# Power.net
KiCad netlist of a schematic drawn in Altium Designer
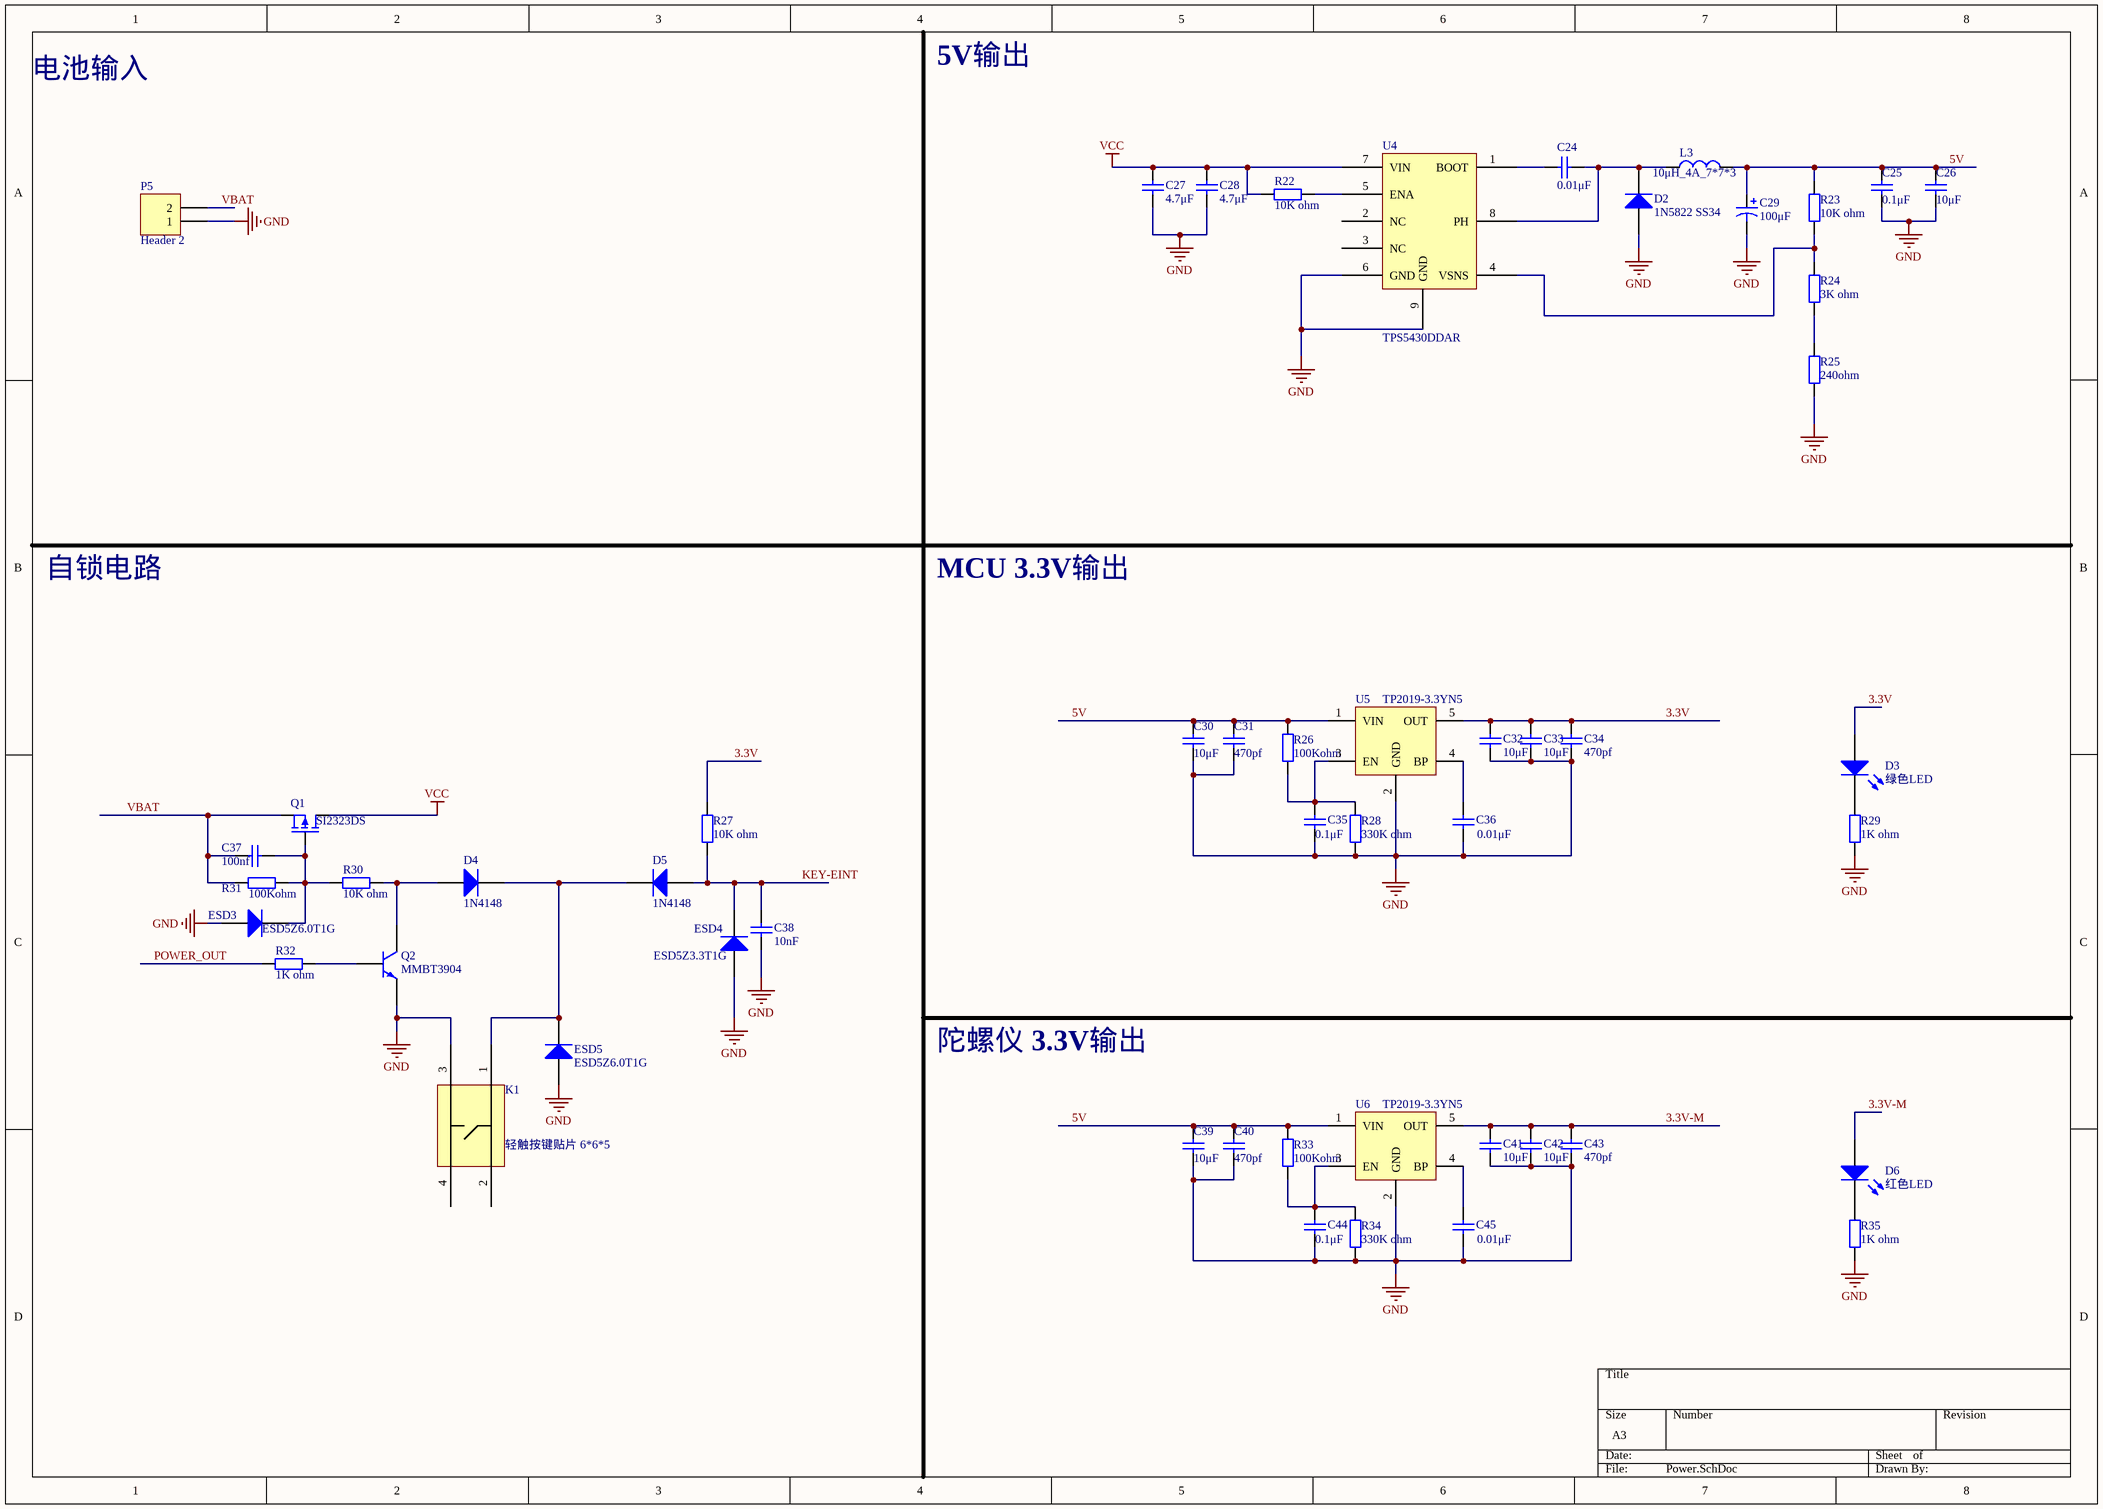
[diagram p0: Power.SchDoc]

(export (version "E")
  (design (tool "Eeschema 10.0.6"))
  (components
    (comp (ref "C24")
      (value "0.01μF")
      (footprint "0603C")
      (description "0.01μF_50V,C0G,5%")
      (libsource (lib "Yang_Lib") (part "Cap_0.01μF_50V_0603"))
    )
    (comp (ref "C25")
      (value "0.1μF")
      (footprint "0603C")
      (description "0.1μF_50V,X7R,±5%")
      (libsource (lib "Yang_Lib") (part "Cap_0.1μF_50V_0603"))
    )
    (comp (ref "C26")
      (value "10μF")
      (footprint "1206C")
      (description "10μF_10V,10%")
      (libsource (lib "Yang_Lib") (part "Cap_10μF_10V_1206"))
    )
    (comp (ref "C27")
      (value "4.7μF")
      (footprint "1206C")
      (description "4.7μF_35VJB,±10%")
      (libsource (lib "Yang_Lib") (part "Cap_4.7μF_35V_1206"))
    )
    (comp (ref "C28")
      (value "4.7μF")
      (footprint "1206C")
      (description "4.7μF_35VJB,±10%")
      (libsource (lib "Yang_Lib") (part "Cap_4.7μF_35V_1206"))
    )
    (comp (ref "C29")
      (value "100μF")
      (footprint "D7343C")
      (description "100μF_16V")
      (libsource (lib "Yang_Lib") (part "Cap_100μF_16V_D7343"))
    )
    (comp (ref "C30")
      (value "10μF")
      (footprint "0603C")
      (description "10μF_35V,X5R,20%")
      (libsource (lib "Yang_Lib") (part "Cap_10μF_35V_0603"))
    )
    (comp (ref "C31")
      (value "470pf")
      (footprint "0603C")
      (description "470pf_50V,X7R,10%")
      (libsource (lib "Yang_Lib") (part "Cap_470pf_50V_0603"))
    )
    (comp (ref "C32")
      (value "10μF")
      (footprint "0603C")
      (description "10μF_35V,X5R,20%")
      (libsource (lib "Yang_Lib") (part "Cap_10μF_35V_0603"))
    )
    (comp (ref "C33")
      (value "10μF")
      (footprint "0603C")
      (description "10μF_35V,X5R,20%")
      (libsource (lib "Yang_Lib") (part "Cap_10μF_35V_0603"))
    )
    (comp (ref "C34")
      (value "470pf")
      (footprint "0603C")
      (description "470pf_50V,X7R,10%")
      (libsource (lib "Yang_Lib") (part "Cap_470pf_50V_0603"))
    )
    (comp (ref "C35")
      (value "0.1μF")
      (footprint "0603C")
      (description "0.1μF_50V,X7R,±5%")
      (libsource (lib "Yang_Lib") (part "Cap_0.1μF_50V_0603"))
    )
    (comp (ref "C36")
      (value "0.01μF")
      (footprint "0603C")
      (description "0.01μF_50V,C0G,5%")
      (libsource (lib "Yang_Lib") (part "Cap_0.01μF_50V_0603"))
    )
    (comp (ref "C37")
      (value "100nf")
      (footprint "0603C")
      (description "100nf_50V,X5R,10%")
      (libsource (lib "Yang_Lib") (part "Cap_100nf_50V_0603"))
    )
    (comp (ref "C38")
      (value "10nF")
      (footprint "0603C")
      (description "10nF/16V,0603")
      (libsource (lib "Yang_Lib") (part "Cap_10nF_16V_0603"))
    )
    (comp (ref "C39")
      (value "10μF")
      (footprint "0603C")
      (description "10μF_35V,X5R,20%")
      (libsource (lib "Yang_Lib") (part "Cap_10μF_35V_0603"))
    )
    (comp (ref "C40")
      (value "470pf")
      (footprint "0603C")
      (description "470pf_50V,X7R,10%")
      (libsource (lib "Yang_Lib") (part "Cap_470pf_50V_0603"))
    )
    (comp (ref "C41")
      (value "10μF")
      (footprint "0603C")
      (description "10μF_35V,X5R,20%")
      (libsource (lib "Yang_Lib") (part "Cap_10μF_35V_0603"))
    )
    (comp (ref "C42")
      (value "10μF")
      (footprint "0603C")
      (description "10μF_35V,X5R,20%")
      (libsource (lib "Yang_Lib") (part "Cap_10μF_35V_0603"))
    )
    (comp (ref "C43")
      (value "470pf")
      (footprint "0603C")
      (description "470pf_50V,X7R,10%")
      (libsource (lib "Yang_Lib") (part "Cap_470pf_50V_0603"))
    )
    (comp (ref "C44")
      (value "0.1μF")
      (footprint "0603C")
      (description "0.1μF_50V,X7R,±5%")
      (libsource (lib "Yang_Lib") (part "Cap_0.1μF_50V_0603"))
    )
    (comp (ref "C45")
      (value "0.01μF")
      (footprint "0603C")
      (description "0.01μF_50V,C0G,5%")
      (libsource (lib "Yang_Lib") (part "Cap_0.01μF_50V_0603"))
    )
    (comp (ref "D2")
      (value "1N5822 SS34")
      (footprint "SMA-small")
      (libsource (lib "Yang_Lib") (part "1N5822 SS34_SMA"))
    )
    (comp (ref "D3")
      (value "绿色LED")
      (footprint "Yang_Lib:0603LED")
      (description "蓝色LED")
      (libsource (lib "FSR_BodyLib") (part "蓝色LED"))
    )
    (comp (ref "D4")
      (value "1N4148")
      (footprint "SOD323")
      (description "1N4148WS")
      (libsource (lib "Yang_Lib") (part "1N4148WS_SOD323"))
    )
    (comp (ref "D5")
      (value "1N4148")
      (footprint "SOD323")
      (description "1N4148WS")
      (libsource (lib "Yang_Lib") (part "1N4148WS_SOD323"))
    )
    (comp (ref "D6")
      (value "红色LED")
      (footprint "Yang_Lib:0603LED")
      (description "蓝色LED")
      (libsource (lib "FSR_BodyLib") (part "蓝色LED"))
    )
    (comp (ref "ESD3")
      (value "ESD5Z6.0T1G")
      (footprint "SOD523")
      (libsource (lib "Yang_Lib") (part "ESD5Z6.0T1G_SOD523"))
    )
    (comp (ref "ESD4")
      (value "ESD5Z3.3T1G")
      (footprint "SOD523")
      (libsource (lib "Yang_Lib") (part "ESD5Z3.3T1G_SOD523"))
    )
    (comp (ref "ESD5")
      (value "ESD5Z6.0T1G")
      (footprint "SOD523")
      (libsource (lib "Yang_Lib") (part "ESD5Z6.0T1G_SOD523"))
    )
    (comp (ref "K1")
      (value "轻触按键贴片 6*6*5")
      (footprint "轻触按键贴片 6*6*5")
      (libsource (lib "Yang_Lib") (part "轻触按键贴片 6*6*5"))
    )
    (comp (ref "L3")
      (value "10μH_4A_7*7*3")
      (footprint "7*7*3mm - 06030")
      (description "10μH_4A")
      (libsource (lib "Yang_Lib") (part "10μH_4A_7*7*3"))
    )
    (comp (ref "P5")
      (value "Header 2")
      (footprint "HDR1X2")
      (description "Header, 2-Pin")
      (fields (field (name "PUBLISHER") "Altium Limited"))
      (libsource (lib "Miscellaneous Connectors") (part "Header 2"))
    )
    (comp (ref "Q1") (value "SI2323DS") (footprint "SOT-23") (libsource (lib "Yang_Lib") (part "SI2323DS")))
    (comp (ref "Q2") (value "MMBT3904") (footprint "SOT-23") (libsource (lib "Yang_Lib") (part "MMBT3904")))
    (comp (ref "R22")
      (value "10K ohm")
      (footprint "0603R")
      (description "10K ohm,1%")
      (libsource (lib "") (part "Res_10K ohm_0603_1"))
    )
    (comp (ref "R23")
      (value "10K ohm")
      (footprint "0603R")
      (description "10K ohm,1%")
      (libsource (lib "Yang_Lib") (part "Res_10K ohm_0603"))
    )
    (comp (ref "R24")
      (value "3K ohm")
      (footprint "0603R")
      (description "3K ohm,1%")
      (libsource (lib "Yang_Lib") (part "Res_3K ohm_0603"))
    )
    (comp (ref "R25")
      (value "240ohm")
      (footprint "0603R")
      (description "240ohm,1%")
      (libsource (lib "Yang_Lib") (part "Res_240ohm_0603"))
    )
    (comp (ref "R26")
      (value "100Kohm")
      (footprint "0603R")
      (description "100K ohm_1%")
      (libsource (lib "") (part "Res_100Kohm_0603_1"))
    )
    (comp (ref "R27")
      (value "10K ohm")
      (footprint "0603R")
      (description "10K ohm,1%")
      (libsource (lib "Yang_Lib") (part "Res_10K ohm_0603"))
    )
    (comp (ref "R28")
      (value "330K ohm")
      (footprint "0603R")
      (description "330K ohm,1%")
      (libsource (lib "Yang_Lib") (part "Res_330K ohm_0603"))
    )
    (comp (ref "R29")
      (value "1K ohm")
      (footprint "0603R")
      (description "1K ohm,1%")
      (libsource (lib "Yang_Lib") (part "Res_1K ohm_0603"))
    )
    (comp (ref "R30")
      (value "10K ohm")
      (footprint "0603R")
      (description "10K ohm,1%")
      (libsource (lib "") (part "Res_10K ohm_0603_1"))
    )
    (comp (ref "R31")
      (value "100Kohm")
      (footprint "0603R")
      (description "100K ohm_5%")
      (libsource (lib "Yang_Lib") (part "Res_100Kohm_0603"))
    )
    (comp (ref "R32")
      (value "1K ohm")
      (footprint "0603R")
      (description "1K ohm,1%")
      (libsource (lib "") (part "Res_1K ohm_0603_1"))
    )
    (comp (ref "R33")
      (value "100Kohm")
      (footprint "0603R")
      (description "100K ohm_1%")
      (libsource (lib "") (part "Res_100Kohm_0603_1"))
    )
    (comp (ref "R34")
      (value "330K ohm")
      (footprint "0603R")
      (description "330K ohm,1%")
      (libsource (lib "Yang_Lib") (part "Res_330K ohm_0603"))
    )
    (comp (ref "R35")
      (value "1K ohm")
      (footprint "0603R")
      (description "1K ohm,1%")
      (libsource (lib "Yang_Lib") (part "Res_1K ohm_0603"))
    )
    (comp (ref "U4")
      (value "TPS5430DDAR")
      (footprint "SOIC8-PAD")
      (libsource (lib "Yang_Lib") (part "TPS5430DDAR"))
    )
    (comp (ref "U5")
      (value "TP2019-3.3YN5")
      (footprint "SOT-23-5")
      (libsource (lib "Yang_Lib") (part "TP2019-3.3YN5"))
    )
    (comp (ref "U6")
      (value "TP2019-3.3YN5")
      (footprint "SOT-23-5")
      (libsource (lib "Yang_Lib") (part "TP2019-3.3YN5"))
    )
  )
  (nets
    (net (code "1") (name "/3.3V") (class "Default")
      (node (ref "C32") (pin "2") (pinfunction "2_2") (pintype "passive"))
      (node (ref "C33") (pin "2") (pinfunction "2_2") (pintype "passive"))
      (node (ref "C34") (pin "2") (pinfunction "2_2") (pintype "passive"))
      (node (ref "D3") (pin "1") (pinfunction "A_1") (pintype "passive"))
      (node (ref "R27") (pin "2") (pinfunction "2_2") (pintype "passive"))
      (node (ref "U5") (pin "5") (pinfunction "OUT_5") (pintype "passive"))
    )
    (net (code "2") (name "/3.3V-M") (class "Default")
      (node (ref "C41") (pin "2") (pinfunction "2_2") (pintype "passive"))
      (node (ref "C42") (pin "2") (pinfunction "2_2") (pintype "passive"))
      (node (ref "C43") (pin "2") (pinfunction "2_2") (pintype "passive"))
      (node (ref "D6") (pin "1") (pinfunction "A_1") (pintype "passive"))
      (node (ref "U6") (pin "5") (pinfunction "OUT_5") (pintype "passive"))
    )
    (net (code "3") (name "/5V") (class "Default")
      (node (ref "C25") (pin "2") (pinfunction "2_2") (pintype "passive"))
      (node (ref "C26") (pin "2") (pinfunction "2_2") (pintype "passive"))
      (node (ref "C29") (pin "1") (pinfunction "1_1") (pintype "passive"))
      (node (ref "C30") (pin "2") (pinfunction "2_2") (pintype "passive"))
      (node (ref "C31") (pin "2") (pinfunction "2_2") (pintype "passive"))
      (node (ref "C39") (pin "2") (pinfunction "2_2") (pintype "passive"))
      (node (ref "C40") (pin "2") (pinfunction "2_2") (pintype "passive"))
      (node (ref "L3") (pin "2") (pinfunction "2_2") (pintype "passive"))
      (node (ref "R23") (pin "2") (pinfunction "2_2") (pintype "passive"))
      (node (ref "R26") (pin "2") (pinfunction "2_2") (pintype "passive"))
      (node (ref "R33") (pin "2") (pinfunction "2_2") (pintype "passive"))
      (node (ref "U5") (pin "1") (pinfunction "VIN_1") (pintype "passive"))
      (node (ref "U6") (pin "1") (pinfunction "VIN_1") (pintype "passive"))
    )
    (net (code "4") (name "/KEY-EINT") (class "Default")
      (node (ref "C38") (pin "2") (pinfunction "2_2") (pintype "passive"))
      (node (ref "D5") (pin "1") (pinfunction "A_1") (pintype "passive"))
      (node (ref "ESD4") (pin "2") (pinfunction "K_2") (pintype "passive"))
      (node (ref "R27") (pin "1") (pinfunction "1_1") (pintype "passive"))
    )
    (net (code "5") (name "/POWER_OUT") (class "Default")
      (node (ref "R32") (pin "1") (pinfunction "1_1") (pintype "passive"))
    )
    (net (code "6") (name "/VBAT") (class "Default")
      (node (ref "C37") (pin "1") (pinfunction "1_1") (pintype "passive"))
      (node (ref "P5") (pin "2") (pinfunction "2_2") (pintype "passive"))
      (node (ref "Q1") (pin "3") (pinfunction "S_3") (pintype "passive"))
      (node (ref "R31") (pin "1") (pinfunction "1_1") (pintype "passive"))
    )
    (net (code "7") (name "GND") (class "Default")
      (node (ref "C25") (pin "1") (pinfunction "1_1") (pintype "passive"))
      (node (ref "C26") (pin "1") (pinfunction "1_1") (pintype "passive"))
      (node (ref "C27") (pin "2") (pinfunction "2_2") (pintype "passive"))
      (node (ref "C28") (pin "1") (pinfunction "1_1") (pintype "passive"))
      (node (ref "C29") (pin "2") (pinfunction "2_2") (pintype "passive"))
      (node (ref "C30") (pin "1") (pinfunction "1_1") (pintype "passive"))
      (node (ref "C31") (pin "1") (pinfunction "1_1") (pintype "passive"))
      (node (ref "C32") (pin "1") (pinfunction "1_1") (pintype "passive"))
      (node (ref "C33") (pin "1") (pinfunction "1_1") (pintype "passive"))
      (node (ref "C34") (pin "1") (pinfunction "1_1") (pintype "passive"))
      (node (ref "C35") (pin "1") (pinfunction "1_1") (pintype "passive"))
      (node (ref "C36") (pin "1") (pinfunction "1_1") (pintype "passive"))
      (node (ref "C38") (pin "1") (pinfunction "1_1") (pintype "passive"))
      (node (ref "C39") (pin "1") (pinfunction "1_1") (pintype "passive"))
      (node (ref "C40") (pin "1") (pinfunction "1_1") (pintype "passive"))
      (node (ref "C41") (pin "1") (pinfunction "1_1") (pintype "passive"))
      (node (ref "C42") (pin "1") (pinfunction "1_1") (pintype "passive"))
      (node (ref "C43") (pin "1") (pinfunction "1_1") (pintype "passive"))
      (node (ref "C44") (pin "1") (pinfunction "1_1") (pintype "passive"))
      (node (ref "C45") (pin "1") (pinfunction "1_1") (pintype "passive"))
      (node (ref "D2") (pin "1") (pinfunction "A_1") (pintype "passive"))
      (node (ref "ESD3") (pin "1") (pinfunction "A_1") (pintype "passive"))
      (node (ref "ESD4") (pin "1") (pinfunction "A_1") (pintype "passive"))
      (node (ref "ESD5") (pin "1") (pinfunction "A_1") (pintype "passive"))
      (node (ref "K1") (pin "3") (pinfunction "3_3") (pintype "passive"))
      (node (ref "P5") (pin "1") (pinfunction "1_1") (pintype "passive"))
      (node (ref "Q2") (pin "3") (pinfunction "E_3") (pintype "passive"))
      (node (ref "R25") (pin "1") (pinfunction "1_1") (pintype "passive"))
      (node (ref "R28") (pin "1") (pinfunction "1_1") (pintype "passive"))
      (node (ref "R29") (pin "1") (pinfunction "1_1") (pintype "passive"))
      (node (ref "R34") (pin "1") (pinfunction "1_1") (pintype "passive"))
      (node (ref "R35") (pin "1") (pinfunction "1_1") (pintype "passive"))
      (node (ref "U4") (pin "6") (pinfunction "GND_6") (pintype "passive"))
      (node (ref "U4") (pin "9") (pinfunction "GND_9") (pintype "passive"))
      (node (ref "U5") (pin "2") (pinfunction "GND_2") (pintype "passive"))
      (node (ref "U6") (pin "2") (pinfunction "GND_2") (pintype "passive"))
    )
    (net (code "8") (name "Net-(D2-K)") (class "Default")
      (node (ref "C24") (pin "2") (pinfunction "2_2") (pintype "passive"))
      (node (ref "D2") (pin "2") (pinfunction "K_2") (pintype "passive"))
      (node (ref "L3") (pin "1") (pinfunction "1_1") (pintype "passive"))
      (node (ref "U4") (pin "8") (pinfunction "PH_8") (pintype "passive"))
    )
    (net (code "9") (name "Net-(D3-K)") (class "Default")
      (node (ref "D3") (pin "2") (pinfunction "K_2") (pintype "passive"))
      (node (ref "R29") (pin "2") (pinfunction "2_2") (pintype "passive"))
    )
    (net (code "10") (name "Net-(D4-A)") (class "Default")
      (node (ref "D4") (pin "1") (pinfunction "A_1") (pintype "passive"))
      (node (ref "Q2") (pin "2") (pinfunction "C_2") (pintype "passive"))
      (node (ref "R30") (pin "2") (pinfunction "2_2") (pintype "passive"))
    )
    (net (code "11") (name "Net-(D4-K)") (class "Default")
      (node (ref "D4") (pin "2") (pinfunction "K_2") (pintype "passive"))
      (node (ref "D5") (pin "2") (pinfunction "K_2") (pintype "passive"))
      (node (ref "ESD5") (pin "2") (pinfunction "K_2") (pintype "passive"))
      (node (ref "K1") (pin "1") (pinfunction "1_1") (pintype "passive"))
    )
    (net (code "12") (name "Net-(D6-K)") (class "Default")
      (node (ref "D6") (pin "2") (pinfunction "K_2") (pintype "passive"))
      (node (ref "R35") (pin "2") (pinfunction "2_2") (pintype "passive"))
    )
    (net (code "13") (name "Net-(ESD3-K)") (class "Default")
      (node (ref "C37") (pin "2") (pinfunction "2_2") (pintype "passive"))
      (node (ref "ESD3") (pin "2") (pinfunction "K_2") (pintype "passive"))
      (node (ref "Q1") (pin "1") (pinfunction "G_1") (pintype "passive"))
      (node (ref "R30") (pin "1") (pinfunction "1_1") (pintype "passive"))
      (node (ref "R31") (pin "2") (pinfunction "2_2") (pintype "passive"))
    )
    (net (code "14") (name "Net-(Q2-B)") (class "Default")
      (node (ref "Q2") (pin "1") (pinfunction "B_1") (pintype "passive"))
      (node (ref "R32") (pin "2") (pinfunction "2_2") (pintype "passive"))
    )
    (net (code "15") (name "Net-(R24-Pad1)") (class "Default")
      (node (ref "R24") (pin "1") (pinfunction "1_1") (pintype "passive"))
      (node (ref "R25") (pin "2") (pinfunction "2_2") (pintype "passive"))
    )
    (net (code "16") (name "Net-(U4-BOOT)") (class "Default")
      (node (ref "C24") (pin "1") (pinfunction "1_1") (pintype "passive"))
      (node (ref "U4") (pin "1") (pinfunction "BOOT_1") (pintype "passive"))
    )
    (net (code "17") (name "Net-(U4-ENA)") (class "Default")
      (node (ref "R22") (pin "2") (pinfunction "2_2") (pintype "passive"))
      (node (ref "U4") (pin "5") (pinfunction "ENA_5") (pintype "passive"))
    )
    (net (code "18") (name "Net-(U4-VSNS)") (class "Default")
      (node (ref "R23") (pin "1") (pinfunction "1_1") (pintype "passive"))
      (node (ref "R24") (pin "2") (pinfunction "2_2") (pintype "passive"))
      (node (ref "U4") (pin "4") (pinfunction "VSNS_4") (pintype "passive"))
    )
    (net (code "19") (name "Net-(U5-BP)") (class "Default")
      (node (ref "C36") (pin "2") (pinfunction "2_2") (pintype "passive"))
      (node (ref "U5") (pin "4") (pinfunction "BP_4") (pintype "passive"))
    )
    (net (code "20") (name "Net-(U5-EN)") (class "Default")
      (node (ref "C35") (pin "2") (pinfunction "2_2") (pintype "passive"))
      (node (ref "R26") (pin "1") (pinfunction "1_1") (pintype "passive"))
      (node (ref "R28") (pin "2") (pinfunction "2_2") (pintype "passive"))
      (node (ref "U5") (pin "3") (pinfunction "EN_3") (pintype "passive"))
    )
    (net (code "21") (name "Net-(U6-BP)") (class "Default")
      (node (ref "C45") (pin "2") (pinfunction "2_2") (pintype "passive"))
      (node (ref "U6") (pin "4") (pinfunction "BP_4") (pintype "passive"))
    )
    (net (code "22") (name "Net-(U6-EN)") (class "Default")
      (node (ref "C44") (pin "2") (pinfunction "2_2") (pintype "passive"))
      (node (ref "R33") (pin "1") (pinfunction "1_1") (pintype "passive"))
      (node (ref "R34") (pin "2") (pinfunction "2_2") (pintype "passive"))
      (node (ref "U6") (pin "3") (pinfunction "EN_3") (pintype "passive"))
    )
    (net (code "23") (name "VCC") (class "Default")
      (node (ref "C27") (pin "1") (pinfunction "1_1") (pintype "passive"))
      (node (ref "C28") (pin "2") (pinfunction "2_2") (pintype "passive"))
      (node (ref "Q1") (pin "2") (pinfunction "D_2") (pintype "passive"))
      (node (ref "R22") (pin "1") (pinfunction "1_1") (pintype "passive"))
      (node (ref "U4") (pin "7") (pinfunction "VIN_7") (pintype "passive"))
    )
    (net (code "24") (name "unconnected-(K1-Pad2)") (class "Default")
      (node (ref "K1") (pin "2") (pinfunction "2_2") (pintype "passive"))
    )
    (net (code "25") (name "unconnected-(K1-Pad4)") (class "Default")
      (node (ref "K1") (pin "4") (pinfunction "4_4") (pintype "passive"))
    )
    (net (code "26") (name "unconnected-(U4-NC-Pad2)") (class "Default")
      (node (ref "U4") (pin "2") (pinfunction "NC_2") (pintype "passive"))
    )
    (net (code "27") (name "unconnected-(U4-NC-Pad3)") (class "Default")
      (node (ref "U4") (pin "3") (pinfunction "NC_3") (pintype "passive"))
    )
  )
)
